# LTC6362_Schematic.net
KiCad netlist of a schematic drawn in Altium Designer
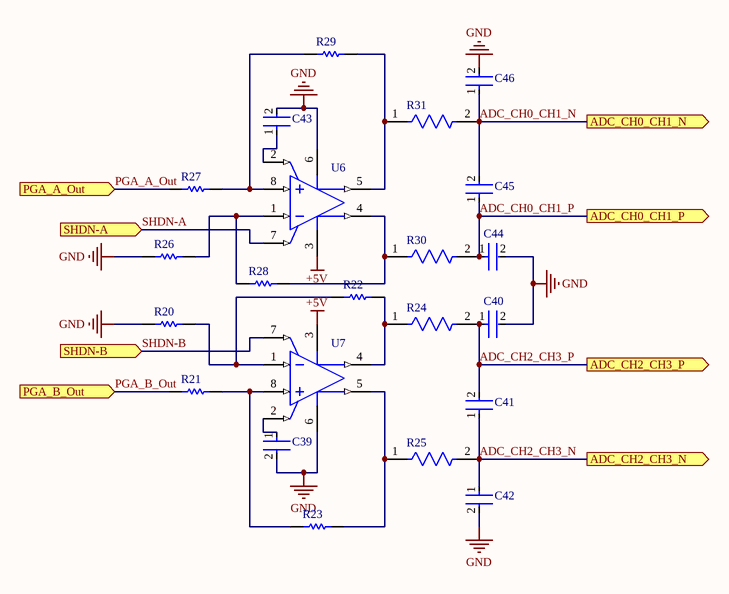
[diagram p0: LTC6362_Schematic.SchDoc]

(export (version "E")
  (design (tool "Eeschema 10.0.6"))
  (components
    (comp (ref "C39")
      (value "GQM1875C2ER10BB12D")
      (footprint "FP-GQM187-0_15-MFG")
      (description "Ceramic Capacitor 0.1pF ±0.1pF 250VDC C0G 0603 Paper T/R")
      (libsource (lib "Altium Content Vault") (part "02cd4be3c70576c341d710602a673aa"))
    )
    (comp (ref "C40")
      (value "CC0603KRX7R9BB392")
      (footprint "FP-CC0603-DA-MFG")
      (description "CAP CER 3900PF 50V X7R 0603")
      (fields (field (name "TOLERANCE") "10%") (field (name "VOLTAGE") "50V"))
      (libsource (lib "Altium Content Vault") (part "11868f565c42a9108669ba33697ecf6"))
    )
    (comp (ref "C41")
      (value "CC0603KRX7R9BB392")
      (footprint "FP-CC0603-DA-MFG")
      (description "CAP CER 3900PF 50V X7R 0603")
      (fields (field (name "TOLERANCE") "10%") (field (name "VOLTAGE") "50V"))
      (libsource (lib "Altium Content Vault") (part "11868f565c42a9108669ba33697ecf6"))
    )
    (comp (ref "C42")
      (value "CC0603KRX7R9BB392")
      (footprint "FP-CC0603-DA-MFG")
      (description "CAP CER 3900PF 50V X7R 0603")
      (fields (field (name "TOLERANCE") "10%") (field (name "VOLTAGE") "50V"))
      (libsource (lib "Altium Content Vault") (part "11868f565c42a9108669ba33697ecf6"))
    )
    (comp (ref "C43")
      (value "GQM1875C2ER10BB12D")
      (footprint "FP-GQM187-0_15-MFG")
      (description "Ceramic Capacitor 0.1pF ±0.1pF 250VDC C0G 0603 Paper T/R")
      (libsource (lib "Altium Content Vault") (part "02cd4be3c70576c341d710602a673aa"))
    )
    (comp (ref "C44")
      (value "CC0603KRX7R9BB392")
      (footprint "FP-CC0603-DA-MFG")
      (description "CAP CER 3900PF 50V X7R 0603")
      (fields (field (name "TOLERANCE") "10%") (field (name "VOLTAGE") "50V"))
      (libsource (lib "Altium Content Vault") (part "11868f565c42a9108669ba33697ecf6"))
    )
    (comp (ref "C45")
      (value "CC0603KRX7R9BB392")
      (footprint "FP-CC0603-DA-MFG")
      (description "CAP CER 3900PF 50V X7R 0603")
      (fields (field (name "TOLERANCE") "10%") (field (name "VOLTAGE") "50V"))
      (libsource (lib "Altium Content Vault") (part "11868f565c42a9108669ba33697ecf6"))
    )
    (comp (ref "C46")
      (value "CC0603KRX7R9BB392")
      (footprint "FP-CC0603-DA-MFG")
      (description "CAP CER 3900PF 50V X7R 0603")
      (fields (field (name "TOLERANCE") "10%") (field (name "VOLTAGE") "50V"))
      (libsource (lib "Altium Content Vault") (part "11868f565c42a9108669ba33697ecf6"))
    )
    (comp (ref "R20")
      (value "ERJ-6ENF1241V")
      (footprint "RESC2013X70X40LL20T20")
      (fields (field (name "MANUFACTURER") "Panasonic"))
      (libsource (lib "Altium Content Vault") (part "RES"))
    )
    (comp (ref "R21")
      (value "ERJ-6ENF1241V")
      (footprint "RESC2013X70X40LL20T20")
      (fields (field (name "MANUFACTURER") "Panasonic"))
      (libsource (lib "Altium Content Vault") (part "RES"))
    )
    (comp (ref "R22")
      (value "RC0805FR-071KL")
      (footprint "RESC2013X60X35ML10T20")
      (description "Chip Resistor, 1 KOhm, +/- 1%, 125 mW, -55 to 155 degC, 0805 (2012 Metric), RoHS, Tape and Reel")
      (fields (field (name "TOLERANCE") "1%") (field (name "MANUFACTURER") "Yageo"))
      (libsource (lib "Altium Content Vault") (part "RES-2"))
    )
    (comp (ref "R23")
      (value "RC0805FR-071KL")
      (footprint "RESC2013X60X35ML10T20")
      (description "Chip Resistor, 1 KOhm, +/- 1%, 125 mW, -55 to 155 degC, 0805 (2012 Metric), RoHS, Tape and Reel")
      (fields (field (name "TOLERANCE") "1%") (field (name "MANUFACTURER") "Yageo"))
      (libsource (lib "Altium Content Vault") (part "RES-2"))
    )
    (comp (ref "R24")
      (value "CRCW060335R7FKEA")
      (footprint "FP-CRCW0603-e3-IPC_B")
      (description "RES Thick Film, 35.7Ω, 1%, 0.1W, 100ppm/°C, 0603")
      (fields (field (name "TOLERANCE") "1%"))
      (libsource (lib "Altium Content Vault") (part "1029c3af85768c4190bb7ad29bc67b5"))
    )
    (comp (ref "R25")
      (value "CRCW060335R7FKEA")
      (footprint "FP-CRCW0603-e3-IPC_B")
      (description "RES Thick Film, 35.7Ω, 1%, 0.1W, 100ppm/°C, 0603")
      (fields (field (name "TOLERANCE") "1%"))
      (libsource (lib "Altium Content Vault") (part "1029c3af85768c4190bb7ad29bc67b5"))
    )
    (comp (ref "R26")
      (value "ERJ-6ENF1241V")
      (footprint "RESC2013X70X40LL20T20")
      (fields (field (name "MANUFACTURER") "Panasonic"))
      (libsource (lib "Altium Content Vault") (part "RES"))
    )
    (comp (ref "R27")
      (value "ERJ-6ENF1241V")
      (footprint "RESC2013X70X40LL20T20")
      (fields (field (name "MANUFACTURER") "Panasonic"))
      (libsource (lib "Altium Content Vault") (part "RES"))
    )
    (comp (ref "R28")
      (value "RC0805FR-071KL")
      (footprint "RESC2013X60X35ML10T20")
      (description "Chip Resistor, 1 KOhm, +/- 1%, 125 mW, -55 to 155 degC, 0805 (2012 Metric), RoHS, Tape and Reel")
      (fields (field (name "TOLERANCE") "1%") (field (name "MANUFACTURER") "Yageo"))
      (libsource (lib "Altium Content Vault") (part "RES-2"))
    )
    (comp (ref "R29")
      (value "RC0805FR-071KL")
      (footprint "RESC2013X60X35ML10T20")
      (description "Chip Resistor, 1 KOhm, +/- 1%, 125 mW, -55 to 155 degC, 0805 (2012 Metric), RoHS, Tape and Reel")
      (fields (field (name "TOLERANCE") "1%") (field (name "MANUFACTURER") "Yageo"))
      (libsource (lib "Altium Content Vault") (part "RES-2"))
    )
    (comp (ref "R30")
      (value "CRCW060335R7FKEA")
      (footprint "FP-CRCW0603-e3-IPC_B")
      (description "RES Thick Film, 35.7Ω, 1%, 0.1W, 100ppm/°C, 0603")
      (fields (field (name "TOLERANCE") "1%"))
      (libsource (lib "Altium Content Vault") (part "1029c3af85768c4190bb7ad29bc67b5"))
    )
    (comp (ref "R31")
      (value "CRCW060335R7FKEA")
      (footprint "FP-CRCW0603-e3-IPC_B")
      (description "RES Thick Film, 35.7Ω, 1%, 0.1W, 100ppm/°C, 0603")
      (fields (field (name "TOLERANCE") "1%"))
      (libsource (lib "Altium Content Vault") (part "1029c3af85768c4190bb7ad29bc67b5"))
    )
    (comp (ref "U6")
      (value "LTC6362HMS8#PBF")
      (footprint "LT-MS8-8_L")
      (fields
        (field (name "LINEAR TECHNOLOGY PART NUMBER") "LTC6362")
        (field (name "MANUFACTURER") "Linear Technology")
      )
      (libsource (lib "LTC6362HMS8_Symbol") (part "CMP-0359-00920-2"))
    )
    (comp (ref "U7")
      (value "LTC6362HMS8#PBF")
      (footprint "LT-MS8-8_L")
      (fields
        (field (name "LINEAR TECHNOLOGY PART NUMBER") "LTC6362")
        (field (name "MANUFACTURER") "Linear Technology")
      )
      (libsource (lib "LTC6362HMS8_Symbol") (part "CMP-0359-00920-2"))
    )
  )
  (nets
    (net (code "1") (name "+5V") (class "Default")
      (node (ref "U6") (pin "3") (pinfunction "V+_3") (pintype "power_in"))
      (node (ref "U7") (pin "3") (pinfunction "V+_3") (pintype "power_in"))
    )
    (net (code "2") (name "/ADC_CH0_CH1_N") (class "Default")
      (node (ref "C45") (pin "2") (pinfunction "2_2") (pintype "passive"))
      (node (ref "C46") (pin "1") (pinfunction "1_1") (pintype "passive"))
      (node (ref "R31") (pin "2") (pinfunction "2_2") (pintype "passive"))
    )
    (net (code "3") (name "/ADC_CH0_CH1_P") (class "Default")
      (node (ref "C44") (pin "1") (pinfunction "1_1") (pintype "passive"))
      (node (ref "C45") (pin "1") (pinfunction "1_1") (pintype "passive"))
      (node (ref "R30") (pin "2") (pinfunction "2_2") (pintype "passive"))
    )
    (net (code "4") (name "/ADC_CH2_CH3_N") (class "Default")
      (node (ref "C41") (pin "1") (pinfunction "1_1") (pintype "passive"))
      (node (ref "C42") (pin "1") (pinfunction "1_1") (pintype "passive"))
      (node (ref "R25") (pin "2") (pinfunction "2_2") (pintype "passive"))
    )
    (net (code "5") (name "/ADC_CH2_CH3_P") (class "Default")
      (node (ref "C40") (pin "1") (pinfunction "1_1") (pintype "passive"))
      (node (ref "C41") (pin "2") (pinfunction "2_2") (pintype "passive"))
      (node (ref "R24") (pin "2") (pinfunction "2_2") (pintype "passive"))
    )
    (net (code "6") (name "/PGA_A_Out") (class "Default")
      (node (ref "R27") (pin "1") (pinfunction "1_1") (pintype "passive"))
    )
    (net (code "7") (name "/PGA_B_Out") (class "Default")
      (node (ref "R21") (pin "1") (pinfunction "1_1") (pintype "passive"))
    )
    (net (code "8") (name "/SHDN-A") (class "Default")
      (node (ref "U6") (pin "7") (pinfunction "~{SHDN}_7") (pintype "input"))
    )
    (net (code "9") (name "/SHDN-B") (class "Default")
      (node (ref "U7") (pin "7") (pinfunction "~{SHDN}_7") (pintype "input"))
    )
    (net (code "10") (name "GND") (class "Default")
      (node (ref "C39") (pin "2") (pinfunction "2_2") (pintype "passive"))
      (node (ref "C40") (pin "2") (pinfunction "2_2") (pintype "passive"))
      (node (ref "C42") (pin "2") (pinfunction "2_2") (pintype "passive"))
      (node (ref "C43") (pin "2") (pinfunction "2_2") (pintype "passive"))
      (node (ref "C44") (pin "2") (pinfunction "2_2") (pintype "passive"))
      (node (ref "C46") (pin "2") (pinfunction "2_2") (pintype "passive"))
      (node (ref "R20") (pin "1") (pinfunction "1_1") (pintype "passive"))
      (node (ref "R26") (pin "1") (pinfunction "1_1") (pintype "passive"))
      (node (ref "U6") (pin "6") (pinfunction "V-_6") (pintype "power_in"))
      (node (ref "U7") (pin "6") (pinfunction "V-_6") (pintype "power_in"))
    )
    (net (code "11") (name "Net-(U6-+IN)") (class "Default")
      (node (ref "R27") (pin "2") (pinfunction "2_2") (pintype "passive"))
      (node (ref "R29") (pin "1") (pinfunction "1_1") (pintype "passive"))
      (node (ref "U6") (pin "8") (pinfunction "+IN_8") (pintype "input"))
    )
    (net (code "12") (name "Net-(U6-+OUT)") (class "Default")
      (node (ref "R28") (pin "2") (pinfunction "2_2") (pintype "passive"))
      (node (ref "R30") (pin "1") (pinfunction "1_1") (pintype "passive"))
      (node (ref "U6") (pin "4") (pinfunction "+OUT_4") (pintype "output"))
    )
    (net (code "13") (name "Net-(U6--IN)") (class "Default")
      (node (ref "R26") (pin "2") (pinfunction "2_2") (pintype "passive"))
      (node (ref "R28") (pin "1") (pinfunction "1_1") (pintype "passive"))
      (node (ref "U6") (pin "1") (pinfunction "-IN_1") (pintype "input"))
    )
    (net (code "14") (name "Net-(U6--OUT)") (class "Default")
      (node (ref "R29") (pin "2") (pinfunction "2_2") (pintype "passive"))
      (node (ref "R31") (pin "1") (pinfunction "1_1") (pintype "passive"))
      (node (ref "U6") (pin "5") (pinfunction "-OUT_5") (pintype "output"))
    )
    (net (code "15") (name "Net-(U6-VOCM)") (class "Default")
      (node (ref "C43") (pin "1") (pinfunction "1_1") (pintype "passive"))
      (node (ref "U6") (pin "2") (pinfunction "VOCM_2") (pintype "input"))
    )
    (net (code "16") (name "Net-(U7-+IN)") (class "Default")
      (node (ref "R21") (pin "2") (pinfunction "2_2") (pintype "passive"))
      (node (ref "R23") (pin "1") (pinfunction "1_1") (pintype "passive"))
      (node (ref "U7") (pin "8") (pinfunction "+IN_8") (pintype "input"))
    )
    (net (code "17") (name "Net-(U7-+OUT)") (class "Default")
      (node (ref "R22") (pin "2") (pinfunction "2_2") (pintype "passive"))
      (node (ref "R24") (pin "1") (pinfunction "1_1") (pintype "passive"))
      (node (ref "U7") (pin "4") (pinfunction "+OUT_4") (pintype "output"))
    )
    (net (code "18") (name "Net-(U7--IN)") (class "Default")
      (node (ref "R20") (pin "2") (pinfunction "2_2") (pintype "passive"))
      (node (ref "R22") (pin "1") (pinfunction "1_1") (pintype "passive"))
      (node (ref "U7") (pin "1") (pinfunction "-IN_1") (pintype "input"))
    )
    (net (code "19") (name "Net-(U7--OUT)") (class "Default")
      (node (ref "R23") (pin "2") (pinfunction "2_2") (pintype "passive"))
      (node (ref "R25") (pin "1") (pinfunction "1_1") (pintype "passive"))
      (node (ref "U7") (pin "5") (pinfunction "-OUT_5") (pintype "output"))
    )
    (net (code "20") (name "Net-(U7-VOCM)") (class "Default")
      (node (ref "C39") (pin "1") (pinfunction "1_1") (pintype "passive"))
      (node (ref "U7") (pin "2") (pinfunction "VOCM_2") (pintype "input"))
    )
  )
)
